# Power_Distribution_-_Center_brake_and_St.net
KiCad netlist of a schematic drawn in Altium Designer
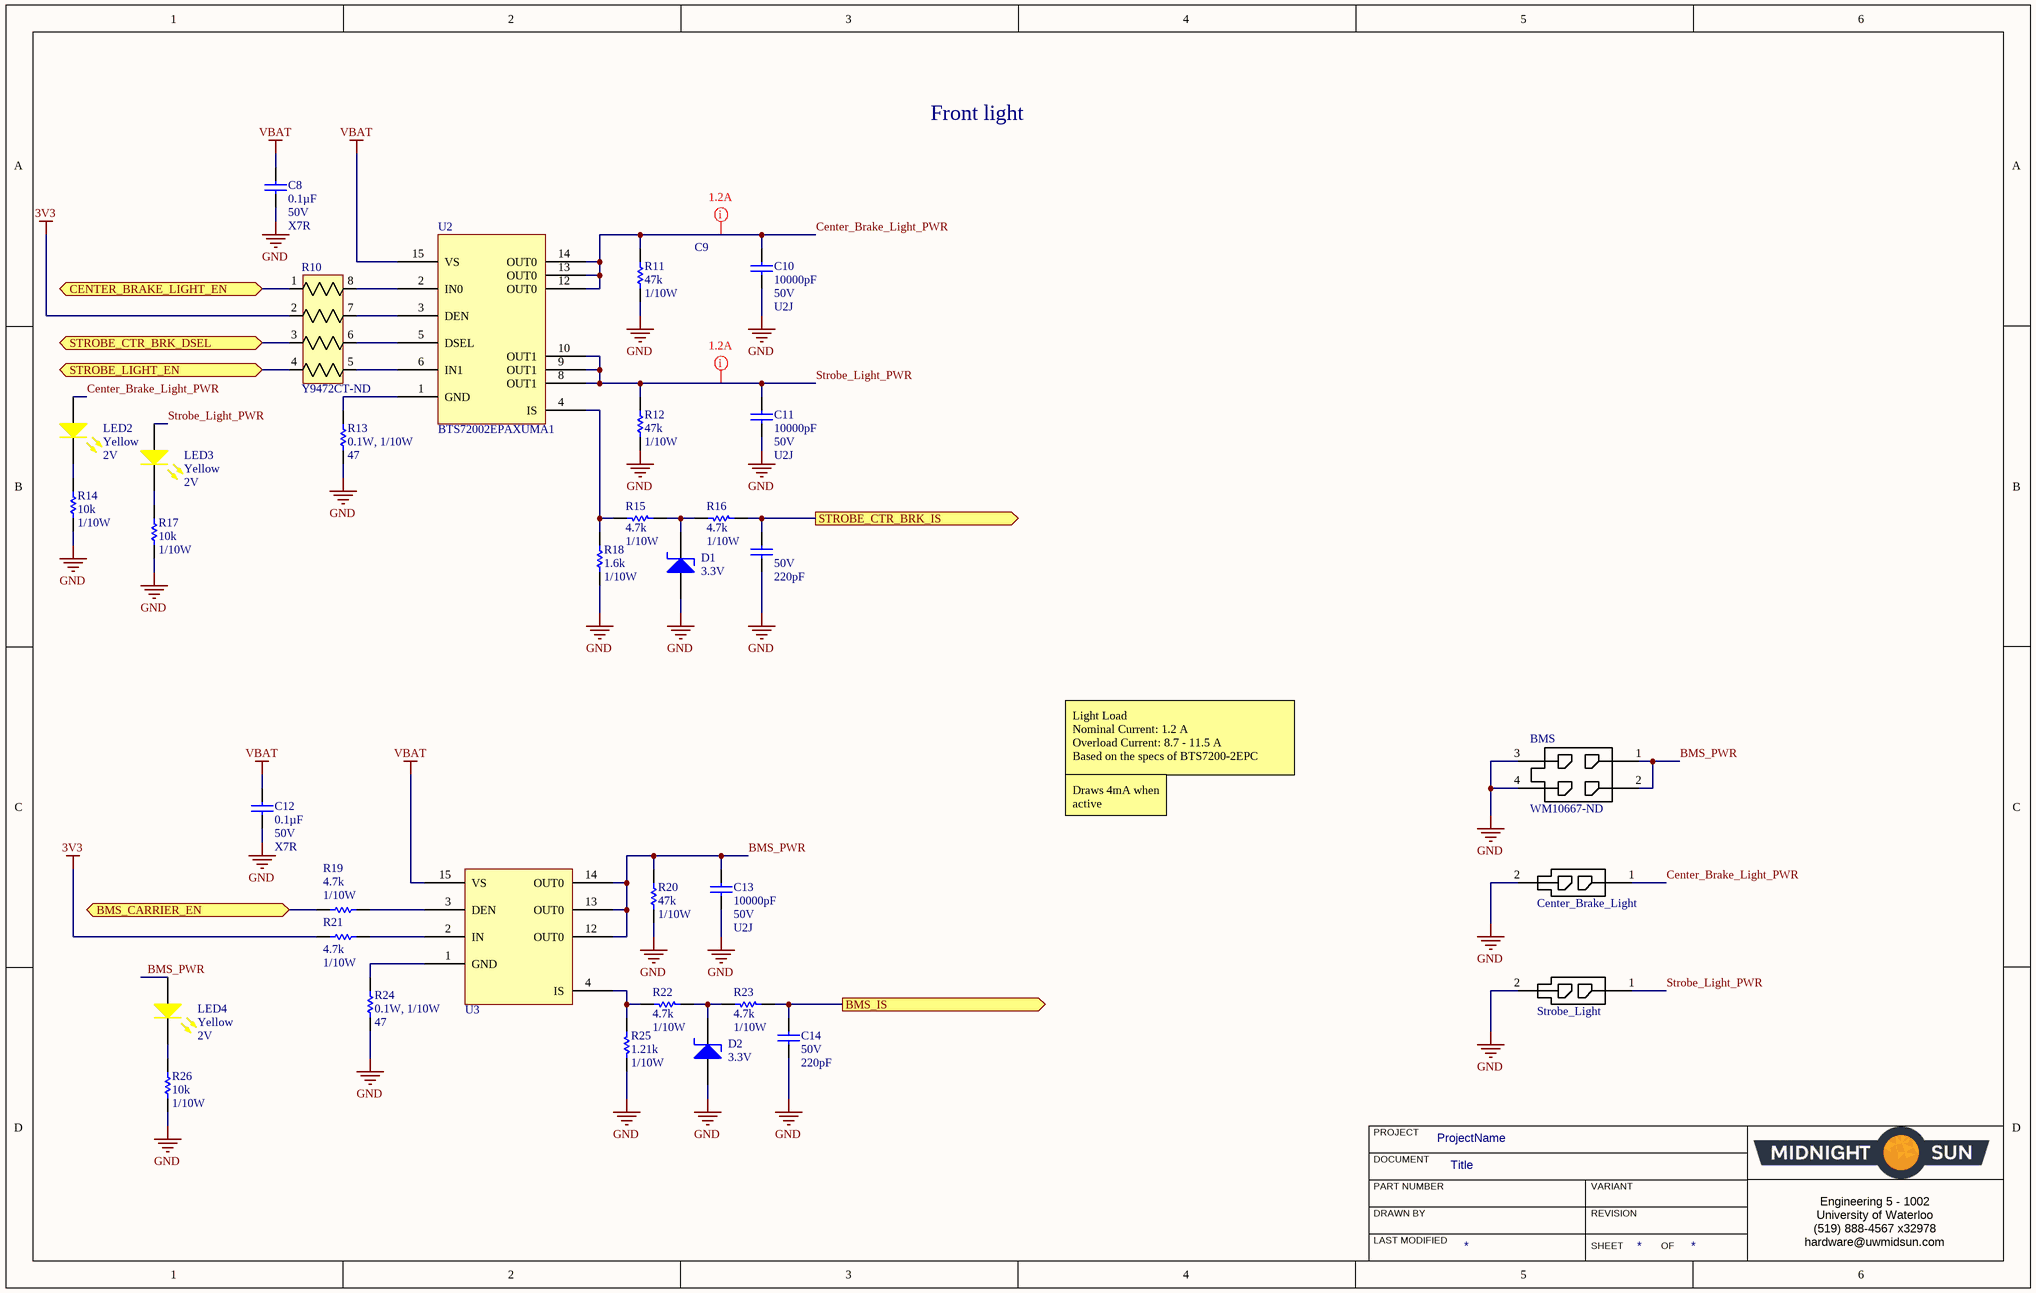
[diagram p0: Power Distribution - Center brake and Strobe light, and BMS.SchDoc]

(export (version "E")
  (design (tool "Eeschema 10.0.6"))
  (components
    (comp (ref "BMS")
      (value "CONN 4POS MICRO-FIT 3mm")
      (footprint "CONN 4POS MICROFIT (2x2)")
      (fields
        (field (name "MANUFACTURER") "Molex, LLC")
        (field (name "MANUFACTURER PART NUMBER") "430450427")
        (field (name "SUPPLIER PART NUMBER 1") "WM10667-ND")
      )
      (libsource (lib "Schematic Diagrams") (part "CONN 4POS MICRO-FIT 3mm"))
    )
    (comp (ref "C8")
      (value "CAP CER 0.1UF 50V 10% X7R 0603")
      (footprint "CAP, 0603")
      (description "0.10µF ±10% 50V Ceramic Capacitor X7R 0603 (1608 Metric)")
      (fields
        (field (name "TOLERANCE") "±10%")
        (field (name "CAPACITANCE") "0.1µF")
        (field (name "VOLTAGE") "50V")
        (field (name "TEMPERATURE COEFFICIENT") "X7R")
      )
      (libsource (lib "Schematic Diagrams") (part "CAP CER 0.1UF 50V 10% X7R 0603"))
    )
    (comp (ref "C9")
      (value "CAP CER 220PF 50V C0G/NP0 0603")
      (footprint "CAP, 0603")
      (description "220pF ±5% 50V Ceramic Capacitor C0G, NP0 0603 (1608 Metric)")
      (fields
        (field (name "MANUFACTURER") "KEMET")
        (field (name "TOLERANCE") "5%")
        (field (name "VOLTAGE RATING") "50V")
        (field (name "CAPACITANCE") "220pF")
      )
      (libsource (lib "Schematic Diagrams") (part "CAP CER 220PF 50V C0G/NP0 0603"))
    )
    (comp (ref "C10")
      (value "CAP CER 10nF 50V 5% X7R 0603")
      (footprint "CAP, 0603")
      (description "10000pF ±5% 50V Ceramic Capacitor U2J 0603 (1608 Metric)")
      (fields
        (field (name "TOLERANCE") "±5%")
        (field (name "CAPACITANCE") "10000pF")
        (field (name "VOLTAGE") "50V")
        (field (name "TEMPERATURE COEFFICIENT") "U2J")
      )
      (libsource (lib "Schematic Diagrams") (part "CAP CER 10nF 50V 5% X7R 0603"))
    )
    (comp (ref "C11")
      (value "CAP CER 10nF 50V 5% X7R 0603")
      (footprint "CAP, 0603")
      (description "10000pF ±5% 50V Ceramic Capacitor U2J 0603 (1608 Metric)")
      (fields
        (field (name "TOLERANCE") "±5%")
        (field (name "CAPACITANCE") "10000pF")
        (field (name "VOLTAGE") "50V")
        (field (name "TEMPERATURE COEFFICIENT") "U2J")
      )
      (libsource (lib "Schematic Diagrams") (part "CAP CER 10nF 50V 5% X7R 0603"))
    )
    (comp (ref "C12")
      (value "CAP CER 0.1UF 50V 10% X7R 0603")
      (footprint "CAP, 0603")
      (description "0.10µF ±10% 50V Ceramic Capacitor X7R 0603 (1608 Metric)")
      (fields
        (field (name "TOLERANCE") "±10%")
        (field (name "CAPACITANCE") "0.1µF")
        (field (name "VOLTAGE") "50V")
        (field (name "TEMPERATURE COEFFICIENT") "X7R")
      )
      (libsource (lib "Schematic Diagrams") (part "CAP CER 0.1UF 50V 10% X7R 0603"))
    )
    (comp (ref "C13")
      (value "CAP CER 10nF 50V 5% X7R 0603")
      (footprint "CAP, 0603")
      (description "10000pF ±5% 50V Ceramic Capacitor U2J 0603 (1608 Metric)")
      (fields
        (field (name "TOLERANCE") "±5%")
        (field (name "CAPACITANCE") "10000pF")
        (field (name "VOLTAGE") "50V")
        (field (name "TEMPERATURE COEFFICIENT") "U2J")
      )
      (libsource (lib "Schematic Diagrams") (part "CAP CER 10nF 50V 5% X7R 0603"))
    )
    (comp (ref "C14")
      (value "CAP CER 220PF 50V C0G/NP0 0603")
      (footprint "CAP, 0603")
      (description "220pF ±5% 50V Ceramic Capacitor C0G, NP0 0603 (1608 Metric)")
      (fields
        (field (name "MANUFACTURER") "KEMET")
        (field (name "TOLERANCE") "5%")
        (field (name "VOLTAGE RATING") "50V")
        (field (name "CAPACITANCE") "220pF")
      )
      (libsource (lib "Schematic Diagrams") (part "CAP CER 220PF 50V C0G/NP0 0603"))
    )
    (comp (ref "Center_Brake_Light")
      (value "CONN 2POS MICRO-FIT 3mm")
      (footprint "CONN, 2POS MICRO-FIT")
      (description "Connector Header Through Hole 2 position")
      (fields (field (name "MANUFACTURER") "Molex") (field (name "MANUFACTURER PART NUMBER") "43045-0227"))
      (libsource (lib "Schematic Diagrams") (part "CONN 2POS MICRO-FIT 3mm"))
    )
    (comp (ref "D1")
      (value "DIODE ZENER 3.3V 200MW SOD323")
      (footprint "sod-323")
      (description "Zener Diode 3.3V 200mW ±5% Surface Mount SOD-323")
      (fields (field (name "VOLTAGE") "3.3V"))
      (libsource (lib "Schematic Diagrams") (part "DIODE ZENER 3.3V 200MW SOD323"))
    )
    (comp (ref "D2")
      (value "DIODE ZENER 3.3V 200MW SOD323")
      (footprint "sod-323")
      (description "Zener Diode 3.3V 200mW ±5% Surface Mount SOD-323")
      (fields (field (name "VOLTAGE") "3.3V"))
      (libsource (lib "Schematic Diagrams") (part "DIODE ZENER 3.3V 200MW SOD323"))
    )
    (comp (ref "LED2")
      (value "LED YELLOW CLEAR 2.1V 0603")
      (footprint "LED_0603")
      (description "Yellow 590nm LED Indication - Discrete 2V 0603 (1608 Metric)")
      (fields
        (field (name "MANUFACTURER") "Wurth Electronics Inc.")
        (field (name "MANUFACTURER PART NUMBER") "150060YS75000")
        (field (name "COLOR") "Yellow")
        (field (name "VOLTAGE - FORWARD (VF) (TYP)") "2V")
      )
      (libsource (lib "Schematic Diagrams") (part "LED YELLOW CLEAR 2.1V 0603"))
    )
    (comp (ref "LED3")
      (value "LED YELLOW CLEAR 2.1V 0603")
      (footprint "LED_0603")
      (description "Yellow 590nm LED Indication - Discrete 2V 0603 (1608 Metric)")
      (fields
        (field (name "MANUFACTURER") "Wurth Electronics Inc.")
        (field (name "MANUFACTURER PART NUMBER") "150060YS75000")
        (field (name "COLOR") "Yellow")
        (field (name "VOLTAGE - FORWARD (VF) (TYP)") "2V")
      )
      (libsource (lib "Schematic Diagrams") (part "LED YELLOW CLEAR 2.1V 0603"))
    )
    (comp (ref "LED4")
      (value "LED YELLOW CLEAR 2.1V 0603")
      (footprint "LED_0603")
      (description "Yellow 590nm LED Indication - Discrete 2V 0603 (1608 Metric)")
      (fields
        (field (name "MANUFACTURER") "Wurth Electronics Inc.")
        (field (name "MANUFACTURER PART NUMBER") "150060YS75000")
        (field (name "COLOR") "Yellow")
        (field (name "VOLTAGE - FORWARD (VF) (TYP)") "2V")
      )
      (libsource (lib "Schematic Diagrams") (part "LED YELLOW CLEAR 2.1V 0603"))
    )
    (comp (ref "R10")
      (value "RES ARRAY 4 RES 4.7K OHM 1206")
      (footprint "RES ARRAY 4RES 1206")
      (fields (field (name "TOLERANCE") "±5%") (field (name "SUPPLIER PART NUMBER 1") "Y9472CT-ND"))
      (libsource (lib "Schematic Diagrams") (part "RES ARRAY 4 RES 4.7K OHM 1206"))
    )
    (comp (ref "R11")
      (value "RES 47K OHM 1% 1/10W 0603")
      (footprint "RES, 0603")
      (description "47 kOhms ±1% 0.1W, 1/10W Chip Resistor 0603 (1608 Metric) Automotive AEC-Q200 Thick Film")
      (fields
        (field (name "MANUFACTURER") "Panasonic")
        (field (name "MANUFACTURER PART NUMBER") "ERJ3EKF4702V")
        (field (name "RESISTANCE") "47k")
        (field (name "POWER RATING") "1/10W")
      )
      (libsource (lib "Schematic Diagrams") (part "RES 47K OHM 1% 1/10W 0603"))
    )
    (comp (ref "R12")
      (value "RES 47K OHM 1% 1/10W 0603")
      (footprint "RES, 0603")
      (description "47 kOhms ±1% 0.1W, 1/10W Chip Resistor 0603 (1608 Metric) Automotive AEC-Q200 Thick Film")
      (fields
        (field (name "MANUFACTURER") "Panasonic")
        (field (name "MANUFACTURER PART NUMBER") "ERJ3EKF4702V")
        (field (name "RESISTANCE") "47k")
        (field (name "POWER RATING") "1/10W")
      )
      (libsource (lib "Schematic Diagrams") (part "RES 47K OHM 1% 1/10W 0603"))
    )
    (comp (ref "R13")
      (value "RES SMD 47 OHM 1% 1/10W 0603")
      (footprint "RES, 0603")
      (fields
        (field (name "TOLERANCE") "±1%")
        (field (name "POWER (WATTS)") "0.1W, 1/10W")
        (field (name "VALUES") "47")
      )
      (libsource (lib "Schematic Diagrams") (part "RES SMD 47 OHM 1% 1/10W 0603"))
    )
    (comp (ref "R14")
      (value "RES 10K OHM 1% 1/10W 0603")
      (footprint "RES, 0603")
      (description "RES SMD 10K OHM 1% 1/10W 0603")
      (fields
        (field (name "TOLERANCE") "±1%")
        (field (name "RESISTANCE") "10k")
        (field (name "POWER") "1/10W")
      )
      (libsource (lib "Schematic Diagrams") (part "RES 10K OHM 1% 1/10W 0603"))
    )
    (comp (ref "R15")
      (value "RES 4.7K OHM 1% 1/10W 0603")
      (footprint "RES, 0603")
      (description "4.7k Ohm ±1% 0.1W, 1/10W Chip Resistor 0603 (1608 Metric) Moisture Resistant Thick Film")
      (fields
        (field (name "TOLERANCE") "±1%")
        (field (name "RESISTANCE (OHMS)") "4.7k")
        (field (name "POWER (WATTS)") "1/10W")
      )
      (libsource (lib "Schematic Diagrams") (part "RES 4.7K OHM 1% 1/10W 0603"))
    )
    (comp (ref "R16")
      (value "RES 4.7K OHM 1% 1/10W 0603")
      (footprint "RES, 0603")
      (description "4.7k Ohm ±1% 0.1W, 1/10W Chip Resistor 0603 (1608 Metric) Moisture Resistant Thick Film")
      (fields
        (field (name "TOLERANCE") "±1%")
        (field (name "RESISTANCE (OHMS)") "4.7k")
        (field (name "POWER (WATTS)") "1/10W")
      )
      (libsource (lib "Schematic Diagrams") (part "RES 4.7K OHM 1% 1/10W 0603"))
    )
    (comp (ref "R17")
      (value "RES 10K OHM 1% 1/10W 0603")
      (footprint "RES, 0603")
      (description "RES SMD 10K OHM 1% 1/10W 0603")
      (fields
        (field (name "TOLERANCE") "±1%")
        (field (name "RESISTANCE") "10k")
        (field (name "POWER") "1/10W")
      )
      (libsource (lib "Schematic Diagrams") (part "RES 10K OHM 1% 1/10W 0603"))
    )
    (comp (ref "R18")
      (value "RES 1.6K OHM 1% 1/10W 0603")
      (footprint "RES, 0603")
      (description "1.6 kOhms ±1% 0.1W, 1/10W Chip Resistor 0603 (1608 Metric) Moisture Resistant Thick Film")
      (fields
        (field (name "MANUFACTURER") "Yageo")
        (field (name "MANUFACTURER PART NUMBER") "RC0603FR-071K6L")
        (field (name "RESISTANCE") "1.6k")
        (field (name "POWER RATING") "1/10W")
      )
      (libsource (lib "Schematic Diagrams") (part "RES 1.6K OHM 1% 1/10W 0603"))
    )
    (comp (ref "R19")
      (value "RES 4.7K OHM 1% 1/10W 0603")
      (footprint "RES, 0603")
      (description "4.7k Ohm ±1% 0.1W, 1/10W Chip Resistor 0603 (1608 Metric) Moisture Resistant Thick Film")
      (fields
        (field (name "TOLERANCE") "±1%")
        (field (name "RESISTANCE (OHMS)") "4.7k")
        (field (name "POWER (WATTS)") "1/10W")
      )
      (libsource (lib "Schematic Diagrams") (part "RES 4.7K OHM 1% 1/10W 0603"))
    )
    (comp (ref "R20")
      (value "RES 47K OHM 1% 1/10W 0603")
      (footprint "RES, 0603")
      (description "47 kOhms ±1% 0.1W, 1/10W Chip Resistor 0603 (1608 Metric) Automotive AEC-Q200 Thick Film")
      (fields
        (field (name "MANUFACTURER") "Panasonic")
        (field (name "MANUFACTURER PART NUMBER") "ERJ3EKF4702V")
        (field (name "RESISTANCE") "47k")
        (field (name "POWER RATING") "1/10W")
      )
      (libsource (lib "Schematic Diagrams") (part "RES 47K OHM 1% 1/10W 0603"))
    )
    (comp (ref "R21")
      (value "RES 4.7K OHM 1% 1/10W 0603")
      (footprint "RES, 0603")
      (description "4.7k Ohm ±1% 0.1W, 1/10W Chip Resistor 0603 (1608 Metric) Moisture Resistant Thick Film")
      (fields
        (field (name "TOLERANCE") "±1%")
        (field (name "RESISTANCE (OHMS)") "4.7k")
        (field (name "POWER (WATTS)") "1/10W")
      )
      (libsource (lib "Schematic Diagrams") (part "RES 4.7K OHM 1% 1/10W 0603"))
    )
    (comp (ref "R22")
      (value "RES 4.7K OHM 1% 1/10W 0603")
      (footprint "RES, 0603")
      (description "4.7k Ohm ±1% 0.1W, 1/10W Chip Resistor 0603 (1608 Metric) Moisture Resistant Thick Film")
      (fields
        (field (name "TOLERANCE") "±1%")
        (field (name "RESISTANCE (OHMS)") "4.7k")
        (field (name "POWER (WATTS)") "1/10W")
      )
      (libsource (lib "Schematic Diagrams") (part "RES 4.7K OHM 1% 1/10W 0603"))
    )
    (comp (ref "R23")
      (value "RES 4.7K OHM 1% 1/10W 0603")
      (footprint "RES, 0603")
      (description "4.7k Ohm ±1% 0.1W, 1/10W Chip Resistor 0603 (1608 Metric) Moisture Resistant Thick Film")
      (fields
        (field (name "TOLERANCE") "±1%")
        (field (name "RESISTANCE (OHMS)") "4.7k")
        (field (name "POWER (WATTS)") "1/10W")
      )
      (libsource (lib "Schematic Diagrams") (part "RES 4.7K OHM 1% 1/10W 0603"))
    )
    (comp (ref "R24")
      (value "RES SMD 47 OHM 1% 1/10W 0603")
      (footprint "RES, 0603")
      (fields
        (field (name "TOLERANCE") "±1%")
        (field (name "POWER (WATTS)") "0.1W, 1/10W")
        (field (name "VALUES") "47")
      )
      (libsource (lib "Schematic Diagrams") (part "RES SMD 47 OHM 1% 1/10W 0603"))
    )
    (comp (ref "R25")
      (value "RES 1.21K OHM 1% 1/10W 0603")
      (footprint "RES, 0603")
      (description "1.21k Ohm ±1% 0.1W, 1/10W Chip Resistor 0603 (1608 Metric) Moisture Resistant Thick Film")
      (fields
        (field (name "TOLERANCE") "±1%")
        (field (name "RESISTANCE") "1.21k")
        (field (name "POWER") "1/10W")
      )
      (libsource (lib "Schematic Diagrams") (part "RES 1.21K OHM 1% 1/10W 0603"))
    )
    (comp (ref "R26")
      (value "RES 10K OHM 1% 1/10W 0603")
      (footprint "RES, 0603")
      (description "RES SMD 10K OHM 1% 1/10W 0603")
      (fields
        (field (name "TOLERANCE") "±1%")
        (field (name "RESISTANCE") "10k")
        (field (name "POWER") "1/10W")
      )
      (libsource (lib "Schematic Diagrams") (part "RES 10K OHM 1% 1/10W 0603"))
    )
    (comp (ref "Strobe_Light")
      (value "CONN 2POS MICRO-FIT 3mm")
      (footprint "CONN, 2POS MICRO-FIT")
      (description "Connector Header Through Hole 2 position")
      (fields (field (name "MANUFACTURER") "Molex") (field (name "MANUFACTURER PART NUMBER") "43045-0227"))
      (libsource (lib "Schematic Diagrams") (part "CONN 2POS MICRO-FIT 3mm"))
    )
    (comp (ref "U2")
      (value "IC LOAD SWITCH BTS7200-2EPA PG-TSDSO-14_1")
      (footprint "IC LOAD SWITCH PG-TSDSO-14-22")
      (description "Power Switch/Driver 1:1 N-Channel 1.2A PG-TSDSO-14-22")
      (fields
        (field (name "MANUFACTURER") "Infineon")
        (field (name "MANUFACTURER PART NUMBER") "BTS72002EPAXUMA1")
      )
      (libsource (lib "Schematic Diagrams") (part "IC LOAD SWITCH BTS7200-2EPA PG-TSDSO-14_1"))
    )
    (comp (ref "U3")
      (value "IC LOAD SWITCH BTS70401EPA PG-TSDSO-14-22")
      (footprint "IC LOAD SWITCH PG-TSDSO-14-22")
      (description "Power Switch/Driver 1:1 N-Channel 4.5A PG-TSDSO-14-22")
      (fields
        (field (name "MANUFACTURER") "Infineon")
        (field (name "MANUFACTURER PART NUMBER") "BTS70401EPAXUMA1")
      )
      (libsource (lib "Schematic Diagrams") (part "IC LOAD SWITCH BTS70401EPA PG-TSDSO-14-22"))
    )
  )
  (nets
    (net (code "1") (name "/BMS_CARRIER_EN") (class "Default")
      (node (ref "R19") (pin "1") (pinfunction "1_1") (pintype "passive"))
    )
    (net (code "2") (name "/BMS_IS") (class "Default")
      (node (ref "C14") (pin "1") (pinfunction "1_1") (pintype "passive"))
      (node (ref "R23") (pin "1") (pinfunction "1_1") (pintype "passive"))
    )
    (net (code "3") (name "/BMS_PWR") (class "Default")
      (node (ref "BMS") (pin "1") (pinfunction "1_1") (pintype "passive"))
      (node (ref "BMS") (pin "2") (pinfunction "2_2") (pintype "passive"))
      (node (ref "C13") (pin "1") (pinfunction "1_1") (pintype "passive"))
      (node (ref "LED4") (pin "1") (pinfunction "A_1") (pintype "passive"))
      (node (ref "R20") (pin "1") (pinfunction "1_1") (pintype "passive"))
      (node (ref "U3") (pin "12") (pinfunction "OUT0_12") (pintype "passive"))
      (node (ref "U3") (pin "13") (pinfunction "OUT0_13") (pintype "passive"))
      (node (ref "U3") (pin "14") (pinfunction "OUT0_14") (pintype "passive"))
    )
    (net (code "4") (name "/CENTER_BRAKE_LIGHT_EN") (class "Default")
      (node (ref "R10") (pin "1") (pinfunction "1_1") (pintype "passive"))
    )
    (net (code "5") (name "/Center_Brake_Light_PWR") (class "Default")
      (node (ref "C10") (pin "1") (pinfunction "1_1") (pintype "passive"))
      (node (ref "Center_Brake_Light") (pin "1") (pinfunction "1_1") (pintype "passive"))
      (node (ref "LED2") (pin "1") (pinfunction "A_1") (pintype "passive"))
      (node (ref "R11") (pin "1") (pinfunction "1_1") (pintype "passive"))
      (node (ref "U2") (pin "12") (pinfunction "OUT0_12") (pintype "passive"))
      (node (ref "U2") (pin "13") (pinfunction "OUT0_13") (pintype "passive"))
      (node (ref "U2") (pin "14") (pinfunction "OUT0_14") (pintype "passive"))
    )
    (net (code "6") (name "/STROBE_CTR_BRK_DSEL") (class "Default")
      (node (ref "R10") (pin "3") (pinfunction "3_3") (pintype "passive"))
    )
    (net (code "7") (name "/STROBE_CTR_BRK_IS") (class "Default")
      (node (ref "C9") (pin "1") (pinfunction "1_1") (pintype "passive"))
      (node (ref "R16") (pin "1") (pinfunction "1_1") (pintype "passive"))
    )
    (net (code "8") (name "/STROBE_LIGHT_EN") (class "Default")
      (node (ref "R10") (pin "4") (pinfunction "4_4") (pintype "passive"))
    )
    (net (code "9") (name "/Strobe_Light_PWR") (class "Default")
      (node (ref "C11") (pin "1") (pinfunction "1_1") (pintype "passive"))
      (node (ref "LED3") (pin "1") (pinfunction "A_1") (pintype "passive"))
      (node (ref "R12") (pin "1") (pinfunction "1_1") (pintype "passive"))
      (node (ref "Strobe_Light") (pin "1") (pinfunction "1_1") (pintype "passive"))
      (node (ref "U2") (pin "10") (pinfunction "OUT1_10") (pintype "passive"))
      (node (ref "U2") (pin "8") (pinfunction "OUT1_8") (pintype "passive"))
      (node (ref "U2") (pin "9") (pinfunction "OUT1_9") (pintype "passive"))
    )
    (net (code "10") (name "3V3") (class "Default")
      (node (ref "R10") (pin "2") (pinfunction "2_2") (pintype "passive"))
      (node (ref "R21") (pin "1") (pinfunction "1_1") (pintype "passive"))
    )
    (net (code "11") (name "GND") (class "Default")
      (node (ref "BMS") (pin "3") (pinfunction "3_3") (pintype "passive"))
      (node (ref "BMS") (pin "4") (pinfunction "4_4") (pintype "passive"))
      (node (ref "C10") (pin "2") (pinfunction "2_2") (pintype "passive"))
      (node (ref "C11") (pin "2") (pinfunction "2_2") (pintype "passive"))
      (node (ref "C12") (pin "2") (pinfunction "2_2") (pintype "passive"))
      (node (ref "C13") (pin "2") (pinfunction "2_2") (pintype "passive"))
      (node (ref "C14") (pin "2") (pinfunction "2_2") (pintype "passive"))
      (node (ref "C8") (pin "2") (pinfunction "2_2") (pintype "passive"))
      (node (ref "C9") (pin "2") (pinfunction "2_2") (pintype "passive"))
      (node (ref "Center_Brake_Light") (pin "2") (pinfunction "2_2") (pintype "passive"))
      (node (ref "D1") (pin "1") (pinfunction "A_1") (pintype "passive"))
      (node (ref "D2") (pin "1") (pinfunction "A_1") (pintype "passive"))
      (node (ref "R11") (pin "2") (pinfunction "2_2") (pintype "passive"))
      (node (ref "R12") (pin "2") (pinfunction "2_2") (pintype "passive"))
      (node (ref "R13") (pin "2") (pinfunction "2_2") (pintype "passive"))
      (node (ref "R14") (pin "2") (pinfunction "2_2") (pintype "passive"))
      (node (ref "R17") (pin "2") (pinfunction "2_2") (pintype "passive"))
      (node (ref "R18") (pin "2") (pinfunction "2_2") (pintype "passive"))
      (node (ref "R20") (pin "2") (pinfunction "2_2") (pintype "passive"))
      (node (ref "R24") (pin "2") (pinfunction "2_2") (pintype "passive"))
      (node (ref "R25") (pin "2") (pinfunction "2_2") (pintype "passive"))
      (node (ref "R26") (pin "2") (pinfunction "2_2") (pintype "passive"))
      (node (ref "Strobe_Light") (pin "2") (pinfunction "2_2") (pintype "passive"))
    )
    (net (code "12") (name "Net-(D1-K)") (class "Default")
      (node (ref "D1") (pin "2") (pinfunction "K_2") (pintype "passive"))
      (node (ref "R15") (pin "1") (pinfunction "1_1") (pintype "passive"))
      (node (ref "R16") (pin "2") (pinfunction "2_2") (pintype "passive"))
    )
    (net (code "13") (name "Net-(D2-K)") (class "Default")
      (node (ref "D2") (pin "2") (pinfunction "K_2") (pintype "passive"))
      (node (ref "R22") (pin "1") (pinfunction "1_1") (pintype "passive"))
      (node (ref "R23") (pin "2") (pinfunction "2_2") (pintype "passive"))
    )
    (net (code "14") (name "Net-(LED2-K)") (class "Default")
      (node (ref "LED2") (pin "2") (pinfunction "K_2") (pintype "passive"))
      (node (ref "R14") (pin "1") (pinfunction "1_1") (pintype "passive"))
    )
    (net (code "15") (name "Net-(LED3-K)") (class "Default")
      (node (ref "LED3") (pin "2") (pinfunction "K_2") (pintype "passive"))
      (node (ref "R17") (pin "1") (pinfunction "1_1") (pintype "passive"))
    )
    (net (code "16") (name "Net-(LED4-K)") (class "Default")
      (node (ref "LED4") (pin "2") (pinfunction "K_2") (pintype "passive"))
      (node (ref "R26") (pin "1") (pinfunction "1_1") (pintype "passive"))
    )
    (net (code "17") (name "Net-(U2-DEN)") (class "Default")
      (node (ref "R10") (pin "7") (pinfunction "7_7") (pintype "passive"))
      (node (ref "U2") (pin "3") (pinfunction "DEN_3") (pintype "passive"))
    )
    (net (code "18") (name "Net-(U2-DSEL)") (class "Default")
      (node (ref "R10") (pin "6") (pinfunction "6_6") (pintype "passive"))
      (node (ref "U2") (pin "5") (pinfunction "DSEL_5") (pintype "passive"))
    )
    (net (code "19") (name "Net-(U2-GND)") (class "Default")
      (node (ref "R13") (pin "1") (pinfunction "1_1") (pintype "passive"))
      (node (ref "U2") (pin "1") (pinfunction "GND_1") (pintype "passive"))
    )
    (net (code "20") (name "Net-(U2-IN0)") (class "Default")
      (node (ref "R10") (pin "8") (pinfunction "8_8") (pintype "passive"))
      (node (ref "U2") (pin "2") (pinfunction "IN0_2") (pintype "passive"))
    )
    (net (code "21") (name "Net-(U2-IN1)") (class "Default")
      (node (ref "R10") (pin "5") (pinfunction "5_5") (pintype "passive"))
      (node (ref "U2") (pin "6") (pinfunction "IN1_6") (pintype "passive"))
    )
    (net (code "22") (name "Net-(U2-IS)") (class "Default")
      (node (ref "R15") (pin "2") (pinfunction "2_2") (pintype "passive"))
      (node (ref "R18") (pin "1") (pinfunction "1_1") (pintype "passive"))
      (node (ref "U2") (pin "4") (pinfunction "IS_4") (pintype "passive"))
    )
    (net (code "23") (name "Net-(U3-DEN)") (class "Default")
      (node (ref "R19") (pin "2") (pinfunction "2_2") (pintype "passive"))
      (node (ref "U3") (pin "3") (pinfunction "DEN_3") (pintype "passive"))
    )
    (net (code "24") (name "Net-(U3-GND)") (class "Default")
      (node (ref "R24") (pin "1") (pinfunction "1_1") (pintype "passive"))
      (node (ref "U3") (pin "1") (pinfunction "GND_1") (pintype "passive"))
    )
    (net (code "25") (name "Net-(U3-IN)") (class "Default")
      (node (ref "R21") (pin "2") (pinfunction "2_2") (pintype "passive"))
      (node (ref "U3") (pin "2") (pinfunction "IN_2") (pintype "passive"))
    )
    (net (code "26") (name "Net-(U3-IS)") (class "Default")
      (node (ref "R22") (pin "2") (pinfunction "2_2") (pintype "passive"))
      (node (ref "R25") (pin "1") (pinfunction "1_1") (pintype "passive"))
      (node (ref "U3") (pin "4") (pinfunction "IS_4") (pintype "passive"))
    )
    (net (code "27") (name "VBAT") (class "Default")
      (node (ref "C12") (pin "1") (pinfunction "1_1") (pintype "passive"))
      (node (ref "C8") (pin "1") (pinfunction "1_1") (pintype "passive"))
      (node (ref "U2") (pin "15") (pinfunction "VS_15") (pintype "passive"))
      (node (ref "U3") (pin "15") (pinfunction "VS_15") (pintype "passive"))
    )
  )
)
